# MySens-easyESP32b-012.net
KiCad netlist of a schematic drawn in EAGLE
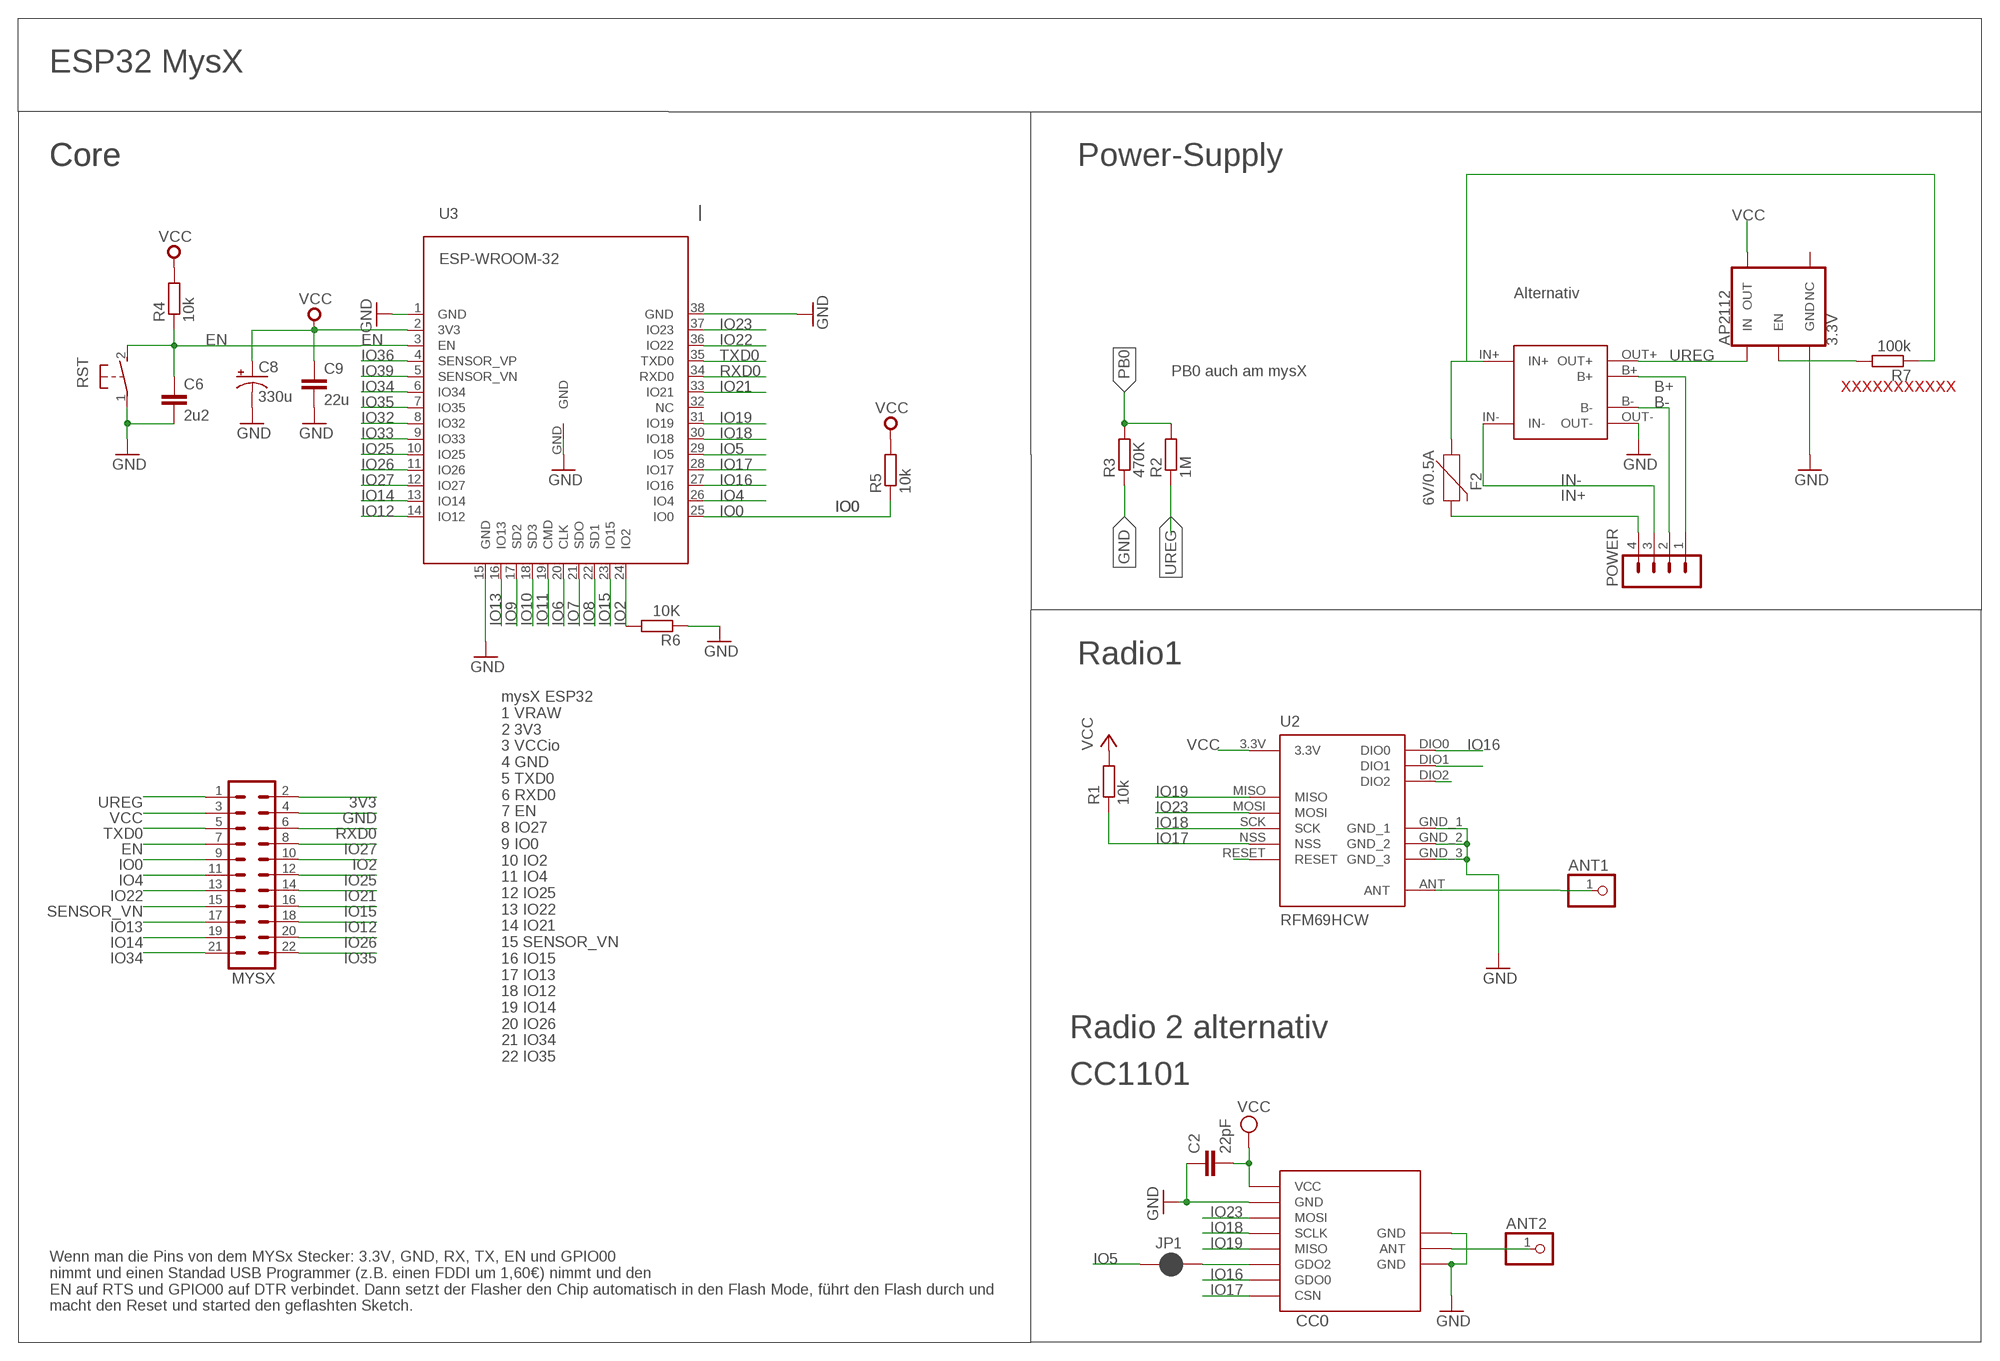
[diagram p0: schematic, sheet 1]

(export (version "E")
  (design (tool "Eeschema 10.0.6"))
  (components
    (comp (ref "ANT1")
      (value "PINHD-1X1")
      (footprint "eagle-import:1X01")
      (libsource (lib "eagle-import") (part "PINHD-1X1"))
    )
    (comp (ref "ANT2")
      (value "PINHD-1X1")
      (footprint "eagle-import:1X01")
      (libsource (lib "eagle-import") (part "PINHD-1X1"))
    )
    (comp (ref "AP2112")
      (value "3.3V")
      (footprint "eagle-import:SOT23-5")
      (libsource (lib "eagle-import") (part "V_REG_AP2112K-3.3V"))
    )
    (comp (ref "C2")
      (value "22pF")
      (footprint "eagle-import:C0805")
      (libsource (lib "eagle-import") (part "C-EUC0805"))
    )
    (comp (ref "C6")
      (value "2u2")
      (footprint "eagle-import:C0805")
      (libsource (lib "eagle-import") (part "rcl@1_C-EUC0805"))
    )
    (comp (ref "C8")
      (value "330u")
      (footprint "eagle-import:VISHAY_C")
      (libsource (lib "eagle-import") (part "CAP_POLSMD"))
    )
    (comp (ref "C9")
      (value "22u")
      (footprint "eagle-import:C0805")
      (libsource (lib "eagle-import") (part "rcl@1_C-EUC0805"))
    )
    (comp (ref "CC0")
      (value "CC1101")
      (footprint "eagle-import:CC1101_MODULE1_SMD")
      (libsource (lib "eagle-import") (part "CC1101_MODULE1SMD"))
    )
    (comp (ref "F2")
      (value "6V/0.5A")
      (footprint "eagle-import:1206")
      (libsource (lib "eagle-import") (part "PPTC_HALF-AMP"))
    )
    (comp (ref "JP1")
      (value "JUMPER-SMT_2_NC_PASTE_NO-SILK")
      (footprint "eagle-import:SMT-JUMPER_2_NC_PASTE_NO-SILK")
      (libsource (lib "eagle-import") (part "JUMPER-SMT_2_NC_PASTE_NO-SILK"))
    )
    (comp (ref "MYSX")
      (value "MA11-2")
      (footprint "eagle-import:MA11-2")
      (libsource (lib "eagle-import") (part "MA11-2"))
    )
    (comp (ref "POWER")
      (value "MA04-1")
      (footprint "eagle-import:MA04-1")
      (libsource (lib "eagle-import") (part "MA04-1"))
    )
    (comp (ref "R1")
      (value "10k")
      (footprint "eagle-import:M0805")
      (libsource (lib "eagle-import") (part "R-EU_M0805"))
    )
    (comp (ref "R2")
      (value "1M")
      (footprint "eagle-import:M0805")
      (libsource (lib "eagle-import") (part "R-EU_M0805"))
    )
    (comp (ref "R3")
      (value "470K")
      (footprint "eagle-import:M0805")
      (libsource (lib "eagle-import") (part "R-EU_M0805"))
    )
    (comp (ref "R4")
      (value "10k")
      (footprint "eagle-import:M0805")
      (libsource (lib "eagle-import") (part "rcl@1_R-EU_M0805"))
    )
    (comp (ref "R5")
      (value "10k")
      (footprint "eagle-import:R0603")
      (libsource (lib "eagle-import") (part "R-EU_R0603"))
    )
    (comp (ref "R6")
      (value "10K")
      (footprint "eagle-import:M0805")
      (libsource (lib "eagle-import") (part "R-EU_M0805"))
    )
    (comp (ref "R7")
      (value "100k")
      (footprint "eagle-import:M0805")
      (libsource (lib "eagle-import") (part "R-EU_M0805"))
    )
    (comp (ref "RST")
      (value "DTSM-3")
      (footprint "eagle-import:DTSM-3")
      (libsource (lib "eagle-import") (part "DTSM-3"))
    )
    (comp (ref "TP4056")
      (value "TP4056-MODULE")
      (footprint "eagle-import:TP4056-LITHIUM-PROTECTED-MODULE")
      (libsource (lib "eagle-import") (part "TP4056-MODULE"))
    )
    (comp (ref "U2")
      (value "RFM69HCW")
      (footprint "eagle-import:RFM69HCW-XXXS2")
      (libsource (lib "eagle-import") (part "RFM69HCW"))
    )
    (comp (ref "U3")
      (value "ESP-WROOM-32")
      (footprint "eagle-import:ESP-WROOM-32")
      (libsource (lib "eagle-import") (part "ESP-WROOM-32"))
    )
  )
  (nets
    (net (code "1") (name "/3V3") (class "Default")
      (node (ref "MYSX") (pin "2") (pinfunction "2_2") (pintype "passive"))
    )
    (net (code "2") (name "/B+") (class "Default")
      (node (ref "POWER") (pin "1") (pinfunction "1_1") (pintype "passive"))
      (node (ref "TP4056") (pin "B+") (pinfunction "B+_B+") (pintype "power_in"))
    )
    (net (code "3") (name "/B-") (class "Default")
      (node (ref "POWER") (pin "2") (pinfunction "2_2") (pintype "passive"))
      (node (ref "TP4056") (pin "B-") (pinfunction "B-_B-") (pintype "power_in"))
    )
    (net (code "4") (name "/EN") (class "Default")
      (node (ref "C6") (pin "1") (pinfunction "1_1") (pintype "passive"))
      (node (ref "MYSX") (pin "7") (pinfunction "7_7") (pintype "passive"))
      (node (ref "R4") (pin "1") (pinfunction "1_1") (pintype "passive"))
      (node (ref "RST") (pin "2") (pinfunction "2_2") (pintype "passive"))
      (node (ref "U3") (pin "3") (pinfunction "EN_3") (pintype "bidirectional"))
    )
    (net (code "5") (name "/IN+") (class "Default")
      (node (ref "F2") (pin "2") (pinfunction "2_2") (pintype "bidirectional"))
      (node (ref "POWER") (pin "4") (pinfunction "4_4") (pintype "passive"))
    )
    (net (code "6") (name "/IN-") (class "Default")
      (node (ref "POWER") (pin "3") (pinfunction "3_3") (pintype "passive"))
      (node (ref "TP4056") (pin "IN-") (pinfunction "IN-_IN-") (pintype "power_in"))
    )
    (net (code "7") (name "/IO0") (class "Default")
      (node (ref "MYSX") (pin "9") (pinfunction "9_9") (pintype "passive"))
      (node (ref "R5") (pin "1") (pinfunction "1_1") (pintype "passive"))
      (node (ref "U3") (pin "25") (pinfunction "IO0_25") (pintype "bidirectional"))
    )
    (net (code "8") (name "/IO2") (class "Default")
      (node (ref "MYSX") (pin "10") (pinfunction "10_10") (pintype "passive"))
      (node (ref "R6") (pin "2") (pinfunction "2_2") (pintype "passive"))
      (node (ref "U3") (pin "24") (pinfunction "IO2_24") (pintype "bidirectional"))
    )
    (net (code "9") (name "/IO4") (class "Default")
      (node (ref "MYSX") (pin "11") (pinfunction "11_11") (pintype "passive"))
      (node (ref "U3") (pin "26") (pinfunction "IO4_26") (pintype "bidirectional"))
    )
    (net (code "10") (name "/IO5") (class "Default")
      (node (ref "JP1") (pin "1") (pinfunction "1_1") (pintype "passive"))
      (node (ref "U3") (pin "29") (pinfunction "IO5_29") (pintype "bidirectional"))
    )
    (net (code "11") (name "/IO6") (class "Default")
      (node (ref "U3") (pin "20") (pinfunction "CLK_20") (pintype "bidirectional"))
    )
    (net (code "12") (name "/IO7") (class "Default")
      (node (ref "U3") (pin "21") (pinfunction "SDO_21") (pintype "bidirectional"))
    )
    (net (code "13") (name "/IO8") (class "Default")
      (node (ref "U3") (pin "22") (pinfunction "SD1_22") (pintype "bidirectional"))
    )
    (net (code "14") (name "/IO9") (class "Default")
      (node (ref "U3") (pin "17") (pinfunction "SD2_17") (pintype "bidirectional"))
    )
    (net (code "15") (name "/IO10") (class "Default")
      (node (ref "U3") (pin "18") (pinfunction "SD3_18") (pintype "bidirectional"))
    )
    (net (code "16") (name "/IO11") (class "Default")
      (node (ref "U3") (pin "19") (pinfunction "CMD_19") (pintype "bidirectional"))
    )
    (net (code "17") (name "/IO12") (class "Default")
      (node (ref "MYSX") (pin "18") (pinfunction "18_18") (pintype "passive"))
      (node (ref "U3") (pin "14") (pinfunction "IO12_14") (pintype "bidirectional"))
    )
    (net (code "18") (name "/IO13") (class "Default")
      (node (ref "MYSX") (pin "17") (pinfunction "17_17") (pintype "passive"))
      (node (ref "U3") (pin "16") (pinfunction "IO13_16") (pintype "bidirectional"))
    )
    (net (code "19") (name "/IO14") (class "Default")
      (node (ref "MYSX") (pin "19") (pinfunction "19_19") (pintype "passive"))
      (node (ref "U3") (pin "13") (pinfunction "IO14_13") (pintype "bidirectional"))
    )
    (net (code "20") (name "/IO15") (class "Default")
      (node (ref "MYSX") (pin "16") (pinfunction "16_16") (pintype "passive"))
      (node (ref "U3") (pin "23") (pinfunction "IO15_23") (pintype "bidirectional"))
    )
    (net (code "21") (name "/IO16") (class "Default")
      (node (ref "CC0") (pin "GDO0") (pinfunction "GDO0_GDO0") (pintype "bidirectional"))
      (node (ref "U2") (pin "DIO0") (pinfunction "DIO0_DIO0") (pintype "bidirectional"))
      (node (ref "U3") (pin "27") (pinfunction "IO16_27") (pintype "bidirectional"))
    )
    (net (code "22") (name "/IO17") (class "Default")
      (node (ref "CC0") (pin "CSN") (pinfunction "CSN_CSN") (pintype "bidirectional"))
      (node (ref "R1") (pin "1") (pinfunction "1_1") (pintype "passive"))
      (node (ref "U2") (pin "NSS") (pinfunction "NSS_NSS") (pintype "input"))
      (node (ref "U3") (pin "28") (pinfunction "IO17_28") (pintype "bidirectional"))
    )
    (net (code "23") (name "/IO18") (class "Default")
      (node (ref "CC0") (pin "SCLK") (pinfunction "SCLK_SCLK") (pintype "bidirectional"))
      (node (ref "U2") (pin "SCK") (pinfunction "SCK_SCK") (pintype "input"))
      (node (ref "U3") (pin "30") (pinfunction "IO18_30") (pintype "bidirectional"))
    )
    (net (code "24") (name "/IO19") (class "Default")
      (node (ref "CC0") (pin "MISO") (pinfunction "MISO_MISO") (pintype "bidirectional"))
      (node (ref "U2") (pin "MISO") (pinfunction "MISO_MISO") (pintype "bidirectional"))
      (node (ref "U3") (pin "31") (pinfunction "IO19_31") (pintype "bidirectional"))
    )
    (net (code "25") (name "/IO21") (class "Default")
      (node (ref "MYSX") (pin "14") (pinfunction "14_14") (pintype "passive"))
      (node (ref "U3") (pin "33") (pinfunction "IO21_33") (pintype "bidirectional"))
    )
    (net (code "26") (name "/IO22") (class "Default")
      (node (ref "MYSX") (pin "13") (pinfunction "13_13") (pintype "passive"))
      (node (ref "U3") (pin "36") (pinfunction "IO22_36") (pintype "bidirectional"))
    )
    (net (code "27") (name "/IO23") (class "Default")
      (node (ref "CC0") (pin "MOSI") (pinfunction "MOSI_MOSI") (pintype "bidirectional"))
      (node (ref "U2") (pin "MOSI") (pinfunction "MOSI_MOSI") (pintype "input"))
      (node (ref "U3") (pin "37") (pinfunction "IO23_37") (pintype "bidirectional"))
    )
    (net (code "28") (name "/IO25") (class "Default")
      (node (ref "MYSX") (pin "12") (pinfunction "12_12") (pintype "passive"))
      (node (ref "U3") (pin "10") (pinfunction "IO25_10") (pintype "bidirectional"))
    )
    (net (code "29") (name "/IO26") (class "Default")
      (node (ref "MYSX") (pin "20") (pinfunction "20_20") (pintype "passive"))
      (node (ref "U3") (pin "11") (pinfunction "IO26_11") (pintype "bidirectional"))
    )
    (net (code "30") (name "/IO27") (class "Default")
      (node (ref "MYSX") (pin "8") (pinfunction "8_8") (pintype "passive"))
      (node (ref "U3") (pin "12") (pinfunction "IO27_12") (pintype "bidirectional"))
    )
    (net (code "31") (name "/IO32") (class "Default")
      (node (ref "U3") (pin "8") (pinfunction "IO32_8") (pintype "bidirectional"))
    )
    (net (code "32") (name "/IO33") (class "Default")
      (node (ref "U3") (pin "9") (pinfunction "IO33_9") (pintype "bidirectional"))
    )
    (net (code "33") (name "/IO34") (class "Default")
      (node (ref "MYSX") (pin "21") (pinfunction "21_21") (pintype "passive"))
      (node (ref "U3") (pin "6") (pinfunction "IO34_6") (pintype "bidirectional"))
    )
    (net (code "34") (name "/IO35") (class "Default")
      (node (ref "MYSX") (pin "22") (pinfunction "22_22") (pintype "passive"))
      (node (ref "U3") (pin "7") (pinfunction "IO35_7") (pintype "bidirectional"))
    )
    (net (code "35") (name "/IO36") (class "Default")
      (node (ref "U3") (pin "4") (pinfunction "SENSOR_VP_4") (pintype "bidirectional"))
    )
    (net (code "36") (name "/IO39") (class "Default")
      (node (ref "U3") (pin "5") (pinfunction "SENSOR_VN_5") (pintype "bidirectional"))
    )
    (net (code "37") (name "/RXD0") (class "Default")
      (node (ref "MYSX") (pin "6") (pinfunction "6_6") (pintype "passive"))
      (node (ref "U3") (pin "34") (pinfunction "RXD0_34") (pintype "bidirectional"))
    )
    (net (code "38") (name "/SENSOR_VN") (class "Default")
      (node (ref "MYSX") (pin "15") (pinfunction "15_15") (pintype "passive"))
    )
    (net (code "39") (name "/TXD0") (class "Default")
      (node (ref "MYSX") (pin "5") (pinfunction "5_5") (pintype "passive"))
      (node (ref "U3") (pin "35") (pinfunction "TXD0_35") (pintype "bidirectional"))
    )
    (net (code "40") (name "GND") (class "Default")
      (node (ref "AP2112") (pin "2") (pinfunction "GND_2") (pintype "input"))
      (node (ref "C2") (pin "1") (pinfunction "1_1") (pintype "passive"))
      (node (ref "C6") (pin "2") (pinfunction "2_2") (pintype "passive"))
      (node (ref "C8") (pin "-") (pinfunction "-_-") (pintype "passive"))
      (node (ref "C9") (pin "2") (pinfunction "2_2") (pintype "passive"))
      (node (ref "CC0") (pin "GND@0") (pinfunction "GND_GND@0") (pintype "power_in"))
      (node (ref "CC0") (pin "GND@1") (pinfunction "GND_GND@1") (pintype "power_in"))
      (node (ref "CC0") (pin "GND@2") (pinfunction "GND_GND@2") (pintype "power_in"))
      (node (ref "MYSX") (pin "4") (pinfunction "4_4") (pintype "passive"))
      (node (ref "R3") (pin "1") (pinfunction "1_1") (pintype "passive"))
      (node (ref "R6") (pin "1") (pinfunction "1_1") (pintype "passive"))
      (node (ref "RST") (pin "1") (pinfunction "1_1") (pintype "passive"))
      (node (ref "TP4056") (pin "OUT-") (pinfunction "OUT-_OUT-") (pintype "power_in"))
      (node (ref "U2") (pin "GND_1") (pinfunction "GND_1_GND_1") (pintype "power_in"))
      (node (ref "U2") (pin "GND_2") (pinfunction "GND_2_GND_2") (pintype "power_in"))
      (node (ref "U2") (pin "GND_3") (pinfunction "GND_3_GND_3") (pintype "power_in"))
      (node (ref "U3") (pin "1") (pinfunction "GND_1") (pintype "bidirectional"))
      (node (ref "U3") (pin "15") (pinfunction "GND_15") (pintype "bidirectional"))
      (node (ref "U3") (pin "38") (pinfunction "GND_38") (pintype "bidirectional"))
      (node (ref "U3") (pin "GND") (pinfunction "GND_GND") (pintype "bidirectional"))
    )
    (net (code "41") (name "Net-(ANT1-Pad1)") (class "Default")
      (node (ref "ANT1") (pin "1") (pinfunction "1_1") (pintype "passive"))
      (node (ref "U2") (pin "ANT") (pinfunction "ANT_ANT") (pintype "passive"))
    )
    (net (code "42") (name "Net-(ANT2-Pad1)") (class "Default")
      (node (ref "ANT2") (pin "1") (pinfunction "1_1") (pintype "passive"))
      (node (ref "CC0") (pin "ANT") (pinfunction "ANT_ANT") (pintype "output"))
    )
    (net (code "43") (name "Net-(AP2112-EN)") (class "Default")
      (node (ref "AP2112") (pin "3") (pinfunction "EN_3") (pintype "input"))
      (node (ref "R7") (pin "2") (pinfunction "2_2") (pintype "passive"))
    )
    (net (code "44") (name "Net-(CC0-PadGDO2)") (class "Default")
      (node (ref "CC0") (pin "GDO2") (pinfunction "GDO2_GDO2") (pintype "bidirectional"))
      (node (ref "JP1") (pin "2") (pinfunction "2_2") (pintype "passive"))
    )
    (net (code "45") (name "Net-(F2-Pad1)") (class "Default")
      (node (ref "F2") (pin "1") (pinfunction "1_1") (pintype "bidirectional"))
      (node (ref "R7") (pin "1") (pinfunction "1_1") (pintype "passive"))
      (node (ref "TP4056") (pin "IN+") (pinfunction "IN+_IN+") (pintype "power_in"))
    )
    (net (code "46") (name "PB0") (class "Default")
      (node (ref "R2") (pin "2") (pinfunction "2_2") (pintype "passive"))
      (node (ref "R3") (pin "2") (pinfunction "2_2") (pintype "passive"))
    )
    (net (code "47") (name "UREG") (class "Default")
      (node (ref "AP2112") (pin "1") (pinfunction "IN_1") (pintype "input"))
      (node (ref "MYSX") (pin "1") (pinfunction "1_1") (pintype "passive"))
      (node (ref "R2") (pin "1") (pinfunction "1_1") (pintype "passive"))
      (node (ref "TP4056") (pin "OUT+") (pinfunction "OUT+_OUT+") (pintype "power_in"))
    )
    (net (code "48") (name "VCC") (class "Default")
      (node (ref "AP2112") (pin "5") (pinfunction "OUT_5") (pintype "passive"))
      (node (ref "C2") (pin "2") (pinfunction "2_2") (pintype "passive"))
      (node (ref "C8") (pin "+") (pinfunction "+_+") (pintype "passive"))
      (node (ref "C9") (pin "1") (pinfunction "1_1") (pintype "passive"))
      (node (ref "CC0") (pin "VCC") (pinfunction "VCC_VCC") (pintype "power_in"))
      (node (ref "MYSX") (pin "3") (pinfunction "3_3") (pintype "passive"))
      (node (ref "R1") (pin "2") (pinfunction "2_2") (pintype "passive"))
      (node (ref "R4") (pin "2") (pinfunction "2_2") (pintype "passive"))
      (node (ref "R5") (pin "2") (pinfunction "2_2") (pintype "passive"))
      (node (ref "U2") (pin "3.3V") (pinfunction "3.3V_3.3V") (pintype "power_in"))
      (node (ref "U3") (pin "2") (pinfunction "3V3_2") (pintype "bidirectional"))
    )
    (net (code "49") (name "unconnected-(AP2112-NC-Pad4)") (class "Default")
      (node (ref "AP2112") (pin "4") (pinfunction "NC_4") (pintype "no_connect"))
    )
    (net (code "50") (name "unconnected-(U2-PadDIO1)") (class "Default")
      (node (ref "U2") (pin "DIO1") (pinfunction "DIO1_DIO1") (pintype "bidirectional"))
    )
    (net (code "51") (name "unconnected-(U2-PadDIO2)") (class "Default")
      (node (ref "U2") (pin "DIO2") (pinfunction "DIO2_DIO2") (pintype "bidirectional"))
    )
    (net (code "52") (name "unconnected-(U2-PadRESET)") (class "Default")
      (node (ref "U2") (pin "RESET") (pinfunction "RESET_RESET") (pintype "input"))
    )
    (net (code "53") (name "unconnected-(U3-NC-Pad32)") (class "Default")
      (node (ref "U3") (pin "32") (pinfunction "NC_32") (pintype "bidirectional"))
    )
  )
)
